# GATEWY_PCB.net
KiCad netlist of a schematic drawn in EAGLE
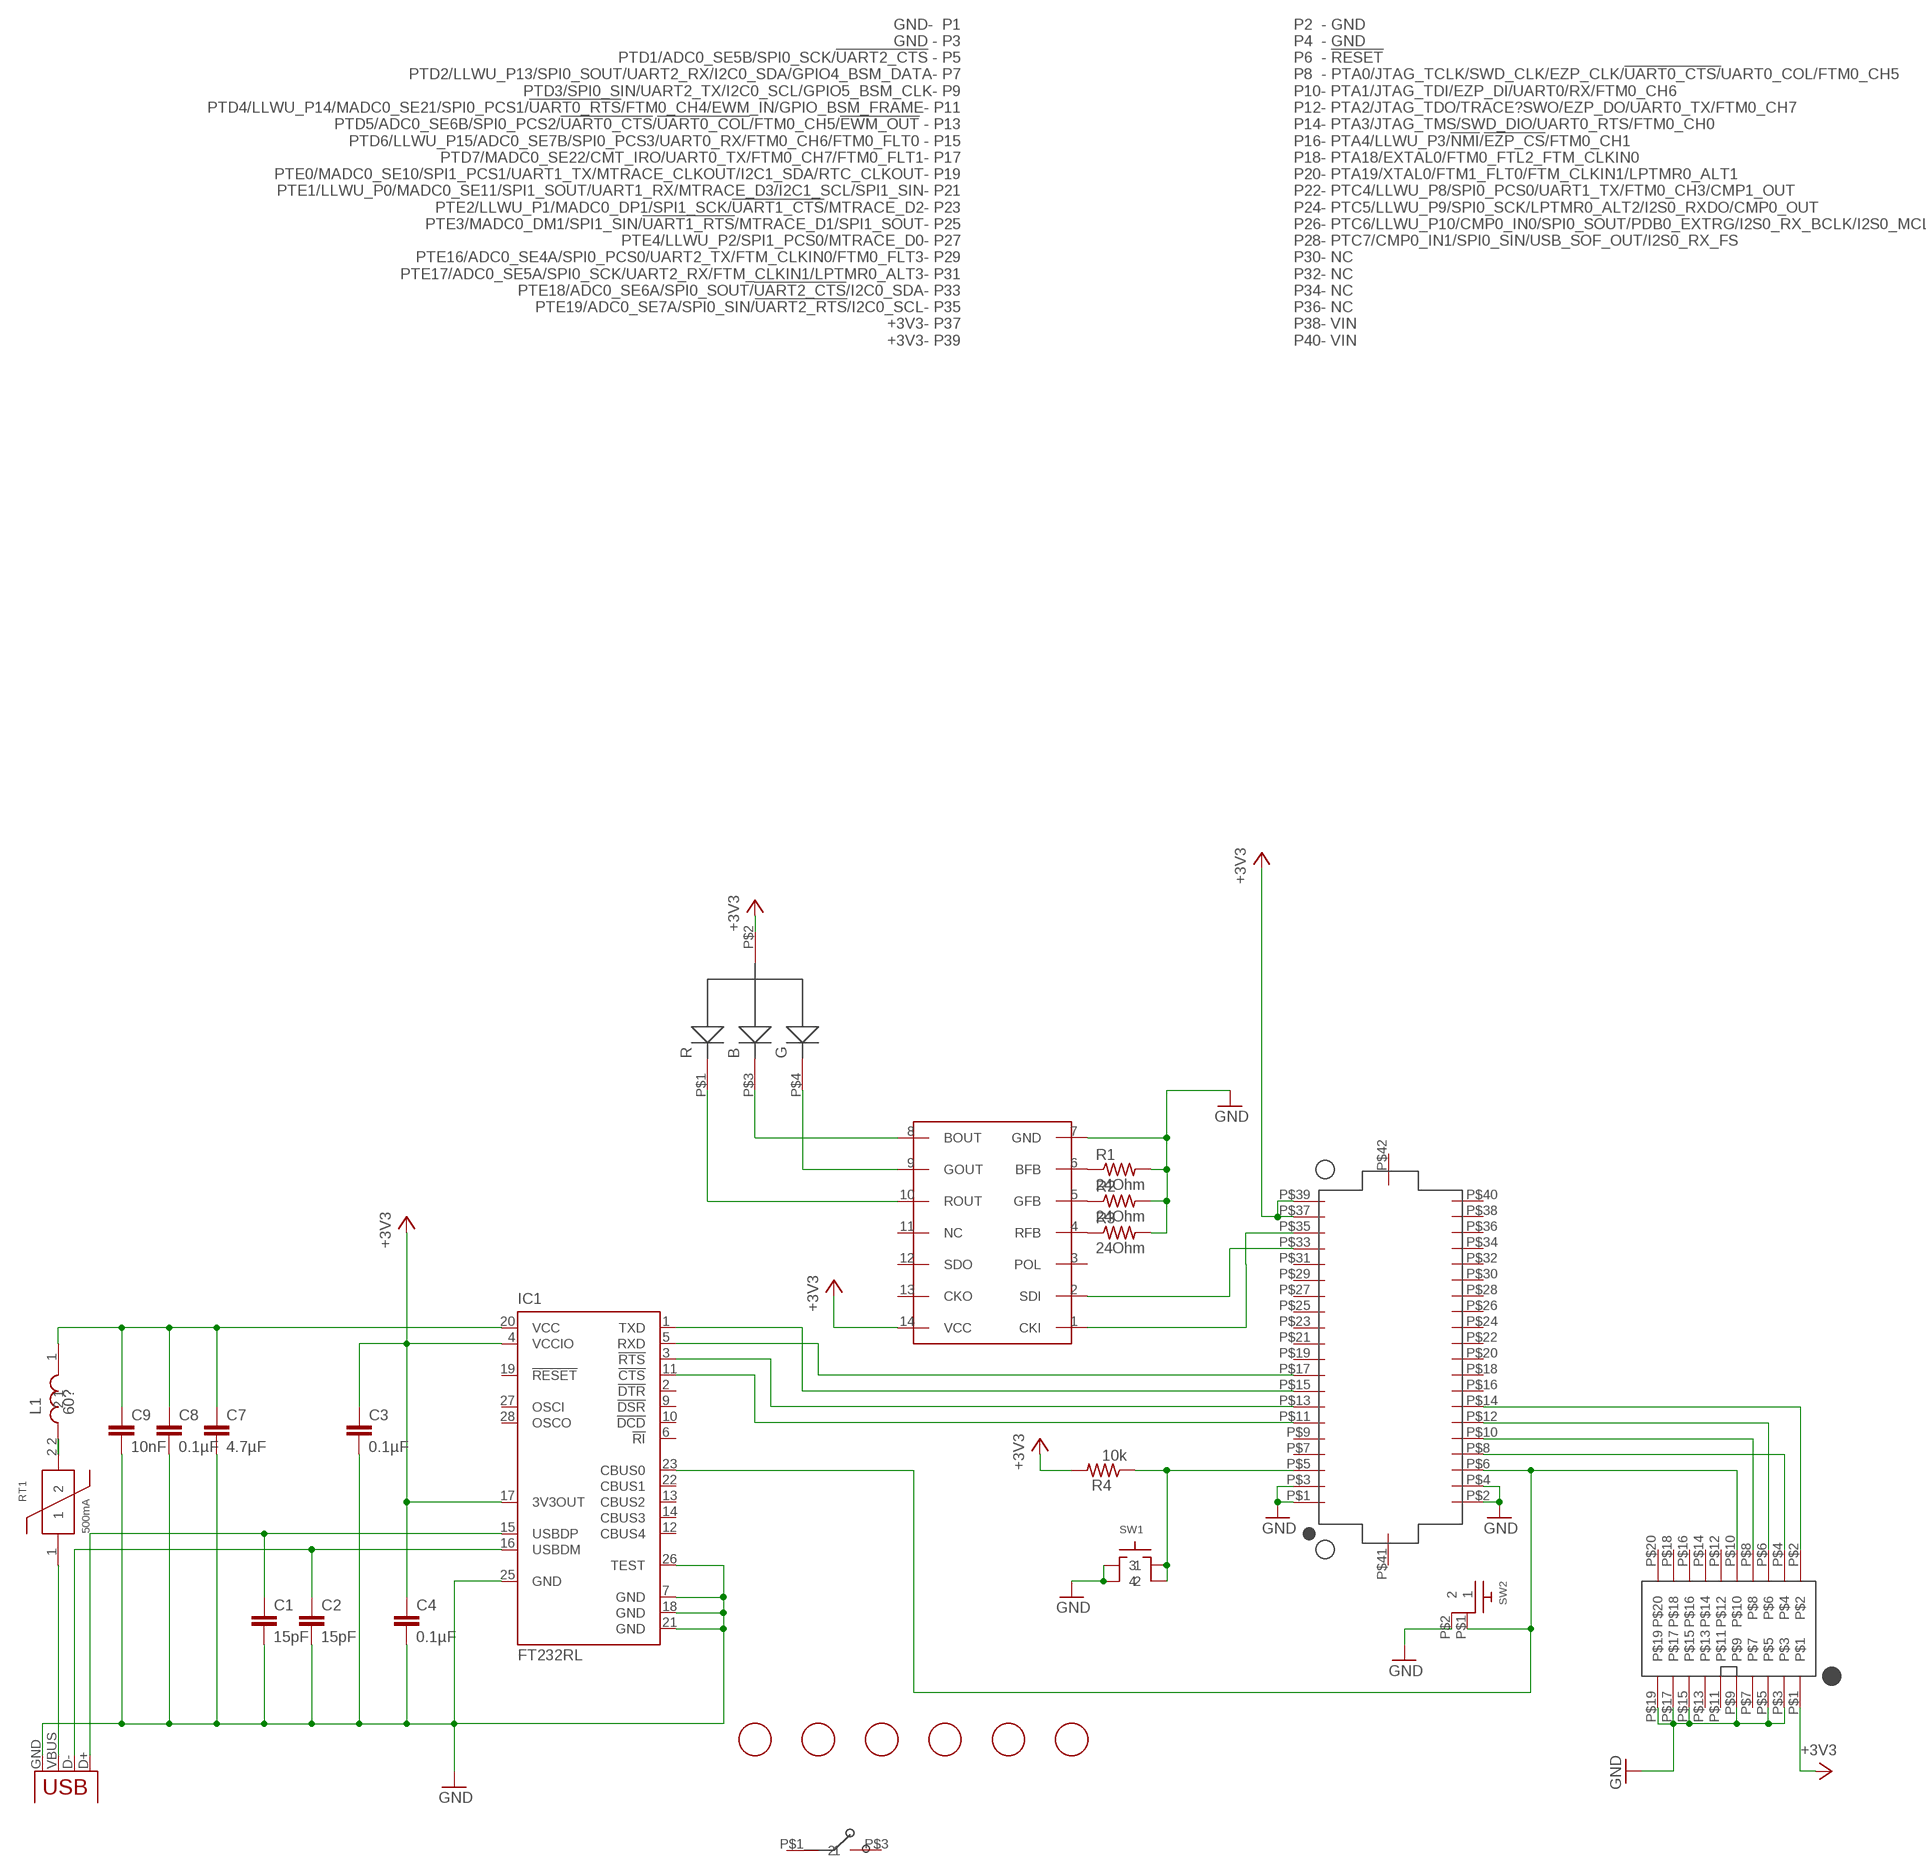
[diagram p0: schematic, sheet 1]

(export (version "E")
  (design (tool "Eeschema 10.0.6"))
  (components
    (comp (ref "AWESOME")
      (value "CJS")
      (footprint "eagle-import:CJS")
      (libsource (lib "eagle-import") (part "CJS"))
    )
    (comp (ref "C1")
      (value "15pF")
      (footprint "eagle-import:RF-C0402")
      (libsource (lib "eagle-import") (part "RF-C0402"))
    )
    (comp (ref "C2")
      (value "15pF")
      (footprint "eagle-import:RF-C0402")
      (libsource (lib "eagle-import") (part "RF-C0402"))
    )
    (comp (ref "C3")
      (value "0.1µF")
      (footprint "eagle-import:RF-C0402")
      (libsource (lib "eagle-import") (part "RF-C0402"))
    )
    (comp (ref "C4")
      (value "0.1µF")
      (footprint "eagle-import:RF-C0402")
      (libsource (lib "eagle-import") (part "RF-C0402"))
    )
    (comp (ref "C7")
      (value "4.7µF")
      (footprint "eagle-import:RF-C0805")
      (libsource (lib "eagle-import") (part "RF-C0805"))
    )
    (comp (ref "C8")
      (value "0.1µF")
      (footprint "eagle-import:RF-C0402")
      (libsource (lib "eagle-import") (part "RF-C0402"))
    )
    (comp (ref "C9")
      (value "10nF")
      (footprint "eagle-import:RF-C0402")
      (libsource (lib "eagle-import") (part "RF-C0402"))
    )
    (comp (ref "IC1")
      (value "FT232RL")
      (footprint "eagle-import:SSOP28")
      (libsource (lib "eagle-import") (part "FT232RL"))
    )
    (comp (ref "JTAG")
      (value "2X10JTAGSMD")
      (footprint "eagle-import:2X10JTAG-SMD")
      (libsource (lib "eagle-import") (part "2X10JTAGSMD"))
    )
    (comp (ref "KW2")
      (value "DF12_F")
      (footprint "eagle-import:DF12_F")
      (fields (field (name "MFGN") "Hirose") (field (name "MFGP") "DF12(3.0)-40DP-0.5V(86)"))
      (libsource (lib "eagle-import") (part "DF12_F"))
    )
    (comp (ref "L1")
      (value "60?")
      (footprint "eagle-import:RF-L0603")
      (libsource (lib "eagle-import") (part "RF-L0603"))
    )
    (comp (ref "LED1")
      (value "RGLBED")
      (footprint "eagle-import:RGBLED")
      (libsource (lib "eagle-import") (part "RGLBED"))
    )
    (comp (ref "R1")
      (value "24Ohm")
      (footprint "eagle-import:RF-C0805")
      (libsource (lib "eagle-import") (part "RF-R0805"))
    )
    (comp (ref "R2")
      (value "24Ohm")
      (footprint "eagle-import:RF-C0805")
      (libsource (lib "eagle-import") (part "RF-R0805"))
    )
    (comp (ref "R3")
      (value "24Ohm")
      (footprint "eagle-import:RF-C0805")
      (libsource (lib "eagle-import") (part "RF-R0805"))
    )
    (comp (ref "R4")
      (value "10k")
      (footprint "eagle-import:RF-C0805")
      (libsource (lib "eagle-import") (part "RF-R0805"))
    )
    (comp (ref "RT1")
      (value "500mA")
      (footprint "eagle-import:C1210")
      (libsource (lib "eagle-import") (part "SMD050F"))
    )
    (comp (ref "SW1")
      (value "SWITCH-TACTILE")
      (footprint "eagle-import:ESWITCH-TL3301PF")
      (libsource (lib "eagle-import") (part "SWITCH-TACTILE"))
    )
    (comp (ref "SW2")
      (value "RA_BUTTON")
      (footprint "eagle-import:RA_BUTTON")
      (libsource (lib "eagle-import") (part "RA_BUTTON"))
    )
    (comp (ref "U$14")
      (value "FIDUCIAL")
      (footprint "eagle-import:FIDUCIAL_1MM")
      (libsource (lib "eagle-import") (part "FIDUCIAL"))
    )
    (comp (ref "U$18")
      (value "FIDUCIAL")
      (footprint "eagle-import:FIDUCIAL_1MM")
      (libsource (lib "eagle-import") (part "FIDUCIAL"))
    )
    (comp (ref "U$25")
      (value "FIDUCIAL")
      (footprint "eagle-import:FIDUCIAL_1MM")
      (libsource (lib "eagle-import") (part "FIDUCIAL"))
    )
    (comp (ref "U$26")
      (value "FIDUCIAL")
      (footprint "eagle-import:FIDUCIAL_1MM")
      (libsource (lib "eagle-import") (part "FIDUCIAL"))
    )
    (comp (ref "U$27")
      (value "FIDUCIAL")
      (footprint "eagle-import:FIDUCIAL_1MM")
      (libsource (lib "eagle-import") (part "FIDUCIAL"))
    )
    (comp (ref "U$28")
      (value "FIDUCIAL")
      (footprint "eagle-import:FIDUCIAL_1MM")
      (libsource (lib "eagle-import") (part "FIDUCIAL"))
    )
    (comp (ref "U1")
      (value "WS2801")
      (footprint "eagle-import:SO14")
      (libsource (lib "eagle-import") (part "WS2801"))
    )
    (comp (ref "X1")
      (value "USBPTH")
      (footprint "eagle-import:USB-B-PTH")
      (libsource (lib "eagle-import") (part "USBPTH"))
    )
  )
  (nets
    (net (code "1") (name "+3V3") (class "Default")
      (node (ref "C3") (pin "1") (pinfunction "1_1") (pintype "passive"))
      (node (ref "C4") (pin "1") (pinfunction "1_1") (pintype "passive"))
      (node (ref "IC1") (pin "17") (pinfunction "3V3OUT_17") (pintype "output"))
      (node (ref "IC1") (pin "4") (pinfunction "VCCIO_4") (pintype "power_in"))
      (node (ref "JTAG") (pin "P$1") (pinfunction "P$1_P$1") (pintype "bidirectional"))
      (node (ref "KW2") (pin "P$37") (pinfunction "+3V3_P$37") (pintype "bidirectional"))
      (node (ref "KW2") (pin "P$39") (pinfunction "+3V3_P$39") (pintype "bidirectional"))
      (node (ref "LED1") (pin "P$2") (pinfunction "ANODE_P$2") (pintype "bidirectional"))
      (node (ref "R4") (pin "2") (pinfunction "2_2") (pintype "passive"))
      (node (ref "U1") (pin "14") (pinfunction "VCC_14") (pintype "bidirectional"))
    )
    (net (code "2") (name "GND") (class "Default")
      (node (ref "C1") (pin "2") (pinfunction "2_2") (pintype "passive"))
      (node (ref "C2") (pin "2") (pinfunction "2_2") (pintype "passive"))
      (node (ref "C3") (pin "2") (pinfunction "2_2") (pintype "passive"))
      (node (ref "C4") (pin "2") (pinfunction "2_2") (pintype "passive"))
      (node (ref "C7") (pin "2") (pinfunction "2_2") (pintype "passive"))
      (node (ref "C8") (pin "2") (pinfunction "2_2") (pintype "passive"))
      (node (ref "C9") (pin "2") (pinfunction "2_2") (pintype "passive"))
      (node (ref "IC1") (pin "18") (pinfunction "GND_18") (pintype "power_in"))
      (node (ref "IC1") (pin "21") (pinfunction "GND_21") (pintype "power_in"))
      (node (ref "IC1") (pin "25") (pinfunction "GND_25") (pintype "power_in"))
      (node (ref "IC1") (pin "26") (pinfunction "TEST_26") (pintype "input"))
      (node (ref "IC1") (pin "7") (pinfunction "GND_7") (pintype "power_in"))
      (node (ref "JTAG") (pin "P$15") (pinfunction "P$15_P$15") (pintype "bidirectional"))
      (node (ref "JTAG") (pin "P$17") (pinfunction "P$17_P$17") (pintype "bidirectional"))
      (node (ref "JTAG") (pin "P$19") (pinfunction "P$19_P$19") (pintype "bidirectional"))
      (node (ref "JTAG") (pin "P$3") (pinfunction "P$3_P$3") (pintype "bidirectional"))
      (node (ref "JTAG") (pin "P$5") (pinfunction "P$5_P$5") (pintype "bidirectional"))
      (node (ref "JTAG") (pin "P$9") (pinfunction "P$9_P$9") (pintype "bidirectional"))
      (node (ref "KW2") (pin "P$1") (pinfunction "GND_P$1") (pintype "bidirectional"))
      (node (ref "KW2") (pin "P$2") (pinfunction "GND_P$2") (pintype "bidirectional"))
      (node (ref "KW2") (pin "P$3") (pinfunction "GND_P$3") (pintype "bidirectional"))
      (node (ref "KW2") (pin "P$4") (pinfunction "GND_P$4") (pintype "bidirectional"))
      (node (ref "R1") (pin "2") (pinfunction "2_2") (pintype "passive"))
      (node (ref "R2") (pin "2") (pinfunction "2_2") (pintype "passive"))
      (node (ref "R3") (pin "2") (pinfunction "2_2") (pintype "passive"))
      (node (ref "SW1") (pin "1") (pinfunction "1_1") (pintype "input"))
      (node (ref "SW1") (pin "2") (pinfunction "2_2") (pintype "input"))
      (node (ref "SW2") (pin "P$2") (pinfunction "2_P$2") (pintype "input"))
      (node (ref "U1") (pin "7") (pinfunction "GND_7") (pintype "bidirectional"))
      (node (ref "X1") (pin "GND") (pinfunction "GND_GND") (pintype "bidirectional"))
    )
    (net (code "3") (name "Net-(IC1-CBUS0)") (class "Default")
      (node (ref "IC1") (pin "23") (pinfunction "CBUS0_23") (pintype "bidirectional"))
      (node (ref "JTAG") (pin "P$10") (pinfunction "P$10_P$10") (pintype "bidirectional"))
      (node (ref "KW2") (pin "P$6") (pinfunction "~{RESET}_P$6") (pintype "bidirectional"))
      (node (ref "SW2") (pin "P$1") (pinfunction "1_P$1") (pintype "input"))
    )
    (net (code "4") (name "Net-(IC1-RXD)") (class "Default")
      (node (ref "IC1") (pin "5") (pinfunction "RXD_5") (pintype "input"))
      (node (ref "KW2") (pin "P$17") (pinfunction "PTD7/MADC0_SE22/CMT_IRO/UART0_TX/FTM0_CH7/FTM0_FLT1_P$17") (pintype "bidirectional"))
    )
    (net (code "5") (name "Net-(IC1-TXD)") (class "Default")
      (node (ref "IC1") (pin "1") (pinfunction "TXD_1") (pintype "output"))
      (node (ref "KW2") (pin "P$15") (pinfunction "PTD6/LLWU_P15/ADC0_SE7B/SPI0_PCS3/UART0_RX/FTM0_CH6/FTM0_FLT0_P$15") (pintype "bidirectional"))
    )
    (net (code "6") (name "Net-(IC1-USBDM)") (class "Default")
      (node (ref "C2") (pin "1") (pinfunction "1_1") (pintype "passive"))
      (node (ref "IC1") (pin "16") (pinfunction "USBDM_16") (pintype "bidirectional"))
      (node (ref "X1") (pin "D-") (pinfunction "D-_D-") (pintype "bidirectional"))
    )
    (net (code "7") (name "Net-(IC1-USBDP)") (class "Default")
      (node (ref "C1") (pin "1") (pinfunction "1_1") (pintype "passive"))
      (node (ref "IC1") (pin "15") (pinfunction "USBDP_15") (pintype "bidirectional"))
      (node (ref "X1") (pin "D+") (pinfunction "D+_D+") (pintype "bidirectional"))
    )
    (net (code "8") (name "Net-(IC1-VCC)") (class "Default")
      (node (ref "C7") (pin "1") (pinfunction "1_1") (pintype "passive"))
      (node (ref "C8") (pin "1") (pinfunction "1_1") (pintype "passive"))
      (node (ref "C9") (pin "1") (pinfunction "1_1") (pintype "passive"))
      (node (ref "IC1") (pin "20") (pinfunction "VCC_20") (pintype "power_in"))
      (node (ref "L1") (pin "1") (pinfunction "1_1") (pintype "bidirectional"))
    )
    (net (code "9") (name "Net-(IC1-~{CTS})") (class "Default")
      (node (ref "IC1") (pin "11") (pinfunction "~{CTS}_11") (pintype "input"))
      (node (ref "KW2") (pin "P$11") (pinfunction "PTD4/LLWU_P14/MADC0_SE21/SPI0_PCS1/~{UART0_RTS}/FTM0_CH4/EWM_IN/GPIO_BSM_FRAME_P$11") (pintype "bidirectional"))
    )
    (net (code "10") (name "Net-(IC1-~{RTS})") (class "Default")
      (node (ref "IC1") (pin "3") (pinfunction "~{RTS}_3") (pintype "output"))
      (node (ref "KW2") (pin "P$13") (pinfunction "PTD5/ADC0_SE6B/SPI0_PCS2/~{UART0_CTS}/~{UART0_COL}/FTM0_CH5/~{EWM_OUT}_P$13") (pintype "bidirectional"))
    )
    (net (code "11") (name "Net-(KW2-PTA0{slash}JTAG_TCLK{slash}SWD_CLK{slash}EZP_CLK{slash}~{UART0_CTS{slash}}UART0_COL{slash}FTM0_CH5)") (class "Default")
      (node (ref "JTAG") (pin "P$4") (pinfunction "P$4_P$4") (pintype "bidirectional"))
      (node (ref "KW2") (pin "P$8") (pinfunction "PTA0/JTAG_TCLK/SWD_CLK/EZP_CLK/~{UART0_CTS/}UART0_COL/FTM0_CH5_P$8") (pintype "bidirectional"))
    )
    (net (code "12") (name "Net-(KW2-PTA1{slash}JTAG_TDI{slash}EZP_DI{slash}UART0{slash}RX{slash}FTM0_CH6)") (class "Default")
      (node (ref "JTAG") (pin "P$8") (pinfunction "P$8_P$8") (pintype "bidirectional"))
      (node (ref "KW2") (pin "P$10") (pinfunction "PTA1/JTAG_TDI/EZP_DI/UART0/RX/FTM0_CH6_P$10") (pintype "bidirectional"))
    )
    (net (code "13") (name "Net-(KW2-PTA2{slash}JTAG_TDO{slash}TRACE?SWO{slash}EZP_DO{slash}UART0_TX{slash}FTM0_CH7)") (class "Default")
      (node (ref "JTAG") (pin "P$6") (pinfunction "P$6_P$6") (pintype "bidirectional"))
      (node (ref "KW2") (pin "P$12") (pinfunction "PTA2/JTAG_TDO/TRACE?SWO/EZP_DO/UART0_TX/FTM0_CH7_P$12") (pintype "bidirectional"))
    )
    (net (code "14") (name "Net-(KW2-PTA3{slash}JTAG_TMS{slash}SWD_DIO{slash}UART0_RTS{slash}FTM0_CH0)") (class "Default")
      (node (ref "JTAG") (pin "P$2") (pinfunction "P$2_P$2") (pintype "bidirectional"))
      (node (ref "KW2") (pin "P$14") (pinfunction "PTA3/JTAG_TMS/SWD_DIO/UART0_RTS/FTM0_CH0_P$14") (pintype "bidirectional"))
    )
    (net (code "15") (name "Net-(KW2-PTD1{slash}ADC0_SE5B{slash}SPI0_SCK{slash}~{UART2_CTS})") (class "Default")
      (node (ref "KW2") (pin "P$5") (pinfunction "PTD1/ADC0_SE5B/SPI0_SCK/~{UART2_CTS}_P$5") (pintype "bidirectional"))
      (node (ref "R4") (pin "1") (pinfunction "1_1") (pintype "passive"))
      (node (ref "SW1") (pin "3") (pinfunction "3_3") (pintype "input"))
      (node (ref "SW1") (pin "4") (pinfunction "4_4") (pintype "input"))
    )
    (net (code "16") (name "Net-(KW2-PTE18{slash}ADC0_SE6A{slash}SPI0_SOUT{slash}~{UART2_CTS}{slash}I2C0_SDA)") (class "Default")
      (node (ref "KW2") (pin "P$33") (pinfunction "PTE18/ADC0_SE6A/SPI0_SOUT/~{UART2_CTS}/I2C0_SDA_P$33") (pintype "bidirectional"))
      (node (ref "U1") (pin "2") (pinfunction "SDI_2") (pintype "bidirectional"))
    )
    (net (code "17") (name "Net-(KW2-PTE19{slash}ADC0_SE7A{slash}SPI0_SIN{slash}~{UART2_RTS}{slash}I2C0_SCL)") (class "Default")
      (node (ref "KW2") (pin "P$35") (pinfunction "PTE19/ADC0_SE7A/SPI0_SIN/~{UART2_RTS}/I2C0_SCL_P$35") (pintype "bidirectional"))
      (node (ref "U1") (pin "1") (pinfunction "CKI_1") (pintype "bidirectional"))
    )
    (net (code "18") (name "Net-(L1-Pad2)") (class "Default")
      (node (ref "L1") (pin "2") (pinfunction "2_2") (pintype "bidirectional"))
      (node (ref "RT1") (pin "2") (pinfunction "2_2") (pintype "bidirectional"))
    )
    (net (code "19") (name "Net-(LED1-BLUE)") (class "Default")
      (node (ref "LED1") (pin "P$3") (pinfunction "BLUE_P$3") (pintype "bidirectional"))
      (node (ref "U1") (pin "8") (pinfunction "BOUT_8") (pintype "bidirectional"))
    )
    (net (code "20") (name "Net-(LED1-GREEN)") (class "Default")
      (node (ref "LED1") (pin "P$4") (pinfunction "GREEN_P$4") (pintype "bidirectional"))
      (node (ref "U1") (pin "9") (pinfunction "GOUT_9") (pintype "bidirectional"))
    )
    (net (code "21") (name "Net-(LED1-RED)") (class "Default")
      (node (ref "LED1") (pin "P$1") (pinfunction "RED_P$1") (pintype "bidirectional"))
      (node (ref "U1") (pin "10") (pinfunction "ROUT_10") (pintype "bidirectional"))
    )
    (net (code "22") (name "Net-(RT1-Pad1)") (class "Default")
      (node (ref "RT1") (pin "1") (pinfunction "1_1") (pintype "bidirectional"))
      (node (ref "X1") (pin "VBUS") (pinfunction "VBUS_VBUS") (pintype "bidirectional"))
    )
    (net (code "23") (name "Net-(U1-BFB)") (class "Default")
      (node (ref "R1") (pin "1") (pinfunction "1_1") (pintype "passive"))
      (node (ref "U1") (pin "6") (pinfunction "BFB_6") (pintype "bidirectional"))
    )
    (net (code "24") (name "Net-(U1-GFB)") (class "Default")
      (node (ref "R2") (pin "1") (pinfunction "1_1") (pintype "passive"))
      (node (ref "U1") (pin "5") (pinfunction "GFB_5") (pintype "bidirectional"))
    )
    (net (code "25") (name "Net-(U1-RFB)") (class "Default")
      (node (ref "R3") (pin "1") (pinfunction "1_1") (pintype "passive"))
      (node (ref "U1") (pin "4") (pinfunction "RFB_4") (pintype "bidirectional"))
    )
    (net (code "26") (name "unconnected-(AWESOME-1-PadP$1)") (class "Default")
      (node (ref "AWESOME") (pin "P$1") (pinfunction "1_P$1") (pintype "bidirectional"))
    )
    (net (code "27") (name "unconnected-(AWESOME-2-PadP$3)") (class "Default")
      (node (ref "AWESOME") (pin "P$3") (pinfunction "2_P$3") (pintype "bidirectional"))
    )
    (net (code "28") (name "unconnected-(IC1-CBUS1-Pad22)") (class "Default")
      (node (ref "IC1") (pin "22") (pinfunction "CBUS1_22") (pintype "bidirectional"))
    )
    (net (code "29") (name "unconnected-(IC1-CBUS2-Pad13)") (class "Default")
      (node (ref "IC1") (pin "13") (pinfunction "CBUS2_13") (pintype "bidirectional"))
    )
    (net (code "30") (name "unconnected-(IC1-CBUS3-Pad14)") (class "Default")
      (node (ref "IC1") (pin "14") (pinfunction "CBUS3_14") (pintype "bidirectional"))
    )
    (net (code "31") (name "unconnected-(IC1-CBUS4-Pad12)") (class "Default")
      (node (ref "IC1") (pin "12") (pinfunction "CBUS4_12") (pintype "bidirectional"))
    )
    (net (code "32") (name "unconnected-(IC1-OSCI-Pad27)") (class "Default")
      (node (ref "IC1") (pin "27") (pinfunction "OSCI_27") (pintype "input"))
    )
    (net (code "33") (name "unconnected-(IC1-OSCO-Pad28)") (class "Default")
      (node (ref "IC1") (pin "28") (pinfunction "OSCO_28") (pintype "output"))
    )
    (net (code "34") (name "unconnected-(IC1-~{DCD}-Pad10)") (class "Default")
      (node (ref "IC1") (pin "10") (pinfunction "~{DCD}_10") (pintype "input"))
    )
    (net (code "35") (name "unconnected-(IC1-~{DSR}-Pad9)") (class "Default")
      (node (ref "IC1") (pin "9") (pinfunction "~{DSR}_9") (pintype "input"))
    )
    (net (code "36") (name "unconnected-(IC1-~{DTR}-Pad2)") (class "Default")
      (node (ref "IC1") (pin "2") (pinfunction "~{DTR}_2") (pintype "output"))
    )
    (net (code "37") (name "unconnected-(IC1-~{RESET}-Pad19)") (class "Default")
      (node (ref "IC1") (pin "19") (pinfunction "~{RESET}_19") (pintype "input"))
    )
    (net (code "38") (name "unconnected-(IC1-~{RI}-Pad6)") (class "Default")
      (node (ref "IC1") (pin "6") (pinfunction "~{RI}_6") (pintype "input"))
    )
    (net (code "39") (name "unconnected-(JTAG-PadP$7)") (class "Default")
      (node (ref "JTAG") (pin "P$7") (pinfunction "P$7_P$7") (pintype "bidirectional"))
    )
    (net (code "40") (name "unconnected-(JTAG-PadP$11)") (class "Default")
      (node (ref "JTAG") (pin "P$11") (pinfunction "P$11_P$11") (pintype "bidirectional"))
    )
    (net (code "41") (name "unconnected-(JTAG-PadP$12)") (class "Default")
      (node (ref "JTAG") (pin "P$12") (pinfunction "P$12_P$12") (pintype "bidirectional"))
    )
    (net (code "42") (name "unconnected-(JTAG-PadP$13)") (class "Default")
      (node (ref "JTAG") (pin "P$13") (pinfunction "P$13_P$13") (pintype "bidirectional"))
    )
    (net (code "43") (name "unconnected-(JTAG-PadP$14)") (class "Default")
      (node (ref "JTAG") (pin "P$14") (pinfunction "P$14_P$14") (pintype "bidirectional"))
    )
    (net (code "44") (name "unconnected-(JTAG-PadP$16)") (class "Default")
      (node (ref "JTAG") (pin "P$16") (pinfunction "P$16_P$16") (pintype "bidirectional"))
    )
    (net (code "45") (name "unconnected-(JTAG-PadP$18)") (class "Default")
      (node (ref "JTAG") (pin "P$18") (pinfunction "P$18_P$18") (pintype "bidirectional"))
    )
    (net (code "46") (name "unconnected-(JTAG-PadP$20)") (class "Default")
      (node (ref "JTAG") (pin "P$20") (pinfunction "P$20_P$20") (pintype "bidirectional"))
    )
    (net (code "47") (name "unconnected-(KW2-NC-PadP$30)") (class "Default")
      (node (ref "KW2") (pin "P$30") (pinfunction "NC_P$30") (pintype "bidirectional"))
    )
    (net (code "48") (name "unconnected-(KW2-NC-PadP$32)") (class "Default")
      (node (ref "KW2") (pin "P$32") (pinfunction "NC_P$32") (pintype "bidirectional"))
    )
    (net (code "49") (name "unconnected-(KW2-NC-PadP$34)") (class "Default")
      (node (ref "KW2") (pin "P$34") (pinfunction "NC_P$34") (pintype "bidirectional"))
    )
    (net (code "50") (name "unconnected-(KW2-NC-PadP$36)") (class "Default")
      (node (ref "KW2") (pin "P$36") (pinfunction "NC_P$36") (pintype "bidirectional"))
    )
    (net (code "51") (name "unconnected-(KW2-PTA4{slash}LLWU_P3{slash}~{NMI}{slash}~{EZP_CS}{slash}FTM0_CH1-PadP$16)") (class "Default")
      (node (ref "KW2") (pin "P$16") (pinfunction "PTA4/LLWU_P3/~{NMI}/~{EZP_CS}/FTM0_CH1_P$16") (pintype "bidirectional"))
    )
    (net (code "52") (name "unconnected-(KW2-PTA18{slash}EXTAL0{slash}FTM0_FTL2_FTM_CLKIN0-PadP$18)") (class "Default")
      (node (ref "KW2") (pin "P$18") (pinfunction "PTA18/EXTAL0/FTM0_FTL2_FTM_CLKIN0_P$18") (pintype "bidirectional"))
    )
    (net (code "53") (name "unconnected-(KW2-PTA19{slash}XTAL0{slash}FTM1_FLT0{slash}FTM_CLKIN1{slash}LPTMR0_ALT1-PadP$20)") (class "Default")
      (node (ref "KW2") (pin "P$20") (pinfunction "PTA19/XTAL0/FTM1_FLT0/FTM_CLKIN1/LPTMR0_ALT1_P$20") (pintype "bidirectional"))
    )
    (net (code "54") (name "unconnected-(KW2-PTC4{slash}LLWU_P8{slash}SPI0_PCS0{slash}UART1_TX{slash}FTM0_CH3{slash}CMP1_OUT-PadP$22)") (class "Default")
      (node (ref "KW2") (pin "P$22") (pinfunction "PTC4/LLWU_P8/SPI0_PCS0/UART1_TX/FTM0_CH3/CMP1_OUT_P$22") (pintype "bidirectional"))
    )
    (net (code "55") (name "unconnected-(KW2-PTC5{slash}LLWU_P8{slash}SPI0_PCS0{slash}UART1_TX{slash}FTM0_CH3{slash}CMP1_OUT-PadP$24)") (class "Default")
      (node (ref "KW2") (pin "P$24") (pinfunction "PTC5/LLWU_P8/SPI0_PCS0/UART1_TX/FTM0_CH3/CMP1_OUT_P$24") (pintype "bidirectional"))
    )
    (net (code "56") (name "unconnected-(KW2-PTC6{slash}LLWU_P10{slash}CMP0_IN0{slash}SPI0_SOUT{slash}PDB0_EXTRG{slash}I2S0_RX_BCLK{slash}I2S0_MCLK-PadP$26)") (class "Default")
      (node (ref "KW2") (pin "P$26") (pinfunction "PTC6/LLWU_P10/CMP0_IN0/SPI0_SOUT/PDB0_EXTRG/I2S0_RX_BCLK/I2S0_MCLK_P$26") (pintype "bidirectional"))
    )
    (net (code "57") (name "unconnected-(KW2-PTC7{slash}CMP0_IN1{slash}SPI0_SIN{slash}USB_SOF_OUT{slash}I2S0_RX_FS-PadP$28)") (class "Default")
      (node (ref "KW2") (pin "P$28") (pinfunction "PTC7/CMP0_IN1/SPI0_SIN/USB_SOF_OUT/I2S0_RX_FS_P$28") (pintype "bidirectional"))
    )
    (net (code "58") (name "unconnected-(KW2-PTD2{slash}LLWU_P13{slash}SPI0_SOUT{slash}UART2_RX{slash}I2C0_SDA{slash}GPIO4_BSM_DATA-PadP$7)") (class "Default")
      (node (ref "KW2") (pin "P$7") (pinfunction "PTD2/LLWU_P13/SPI0_SOUT/UART2_RX/I2C0_SDA/GPIO4_BSM_DATA_P$7") (pintype "bidirectional"))
    )
    (net (code "59") (name "unconnected-(KW2-PTD3{slash}SPI0_SIN{slash}UART2_TX{slash}I2C0_SCL{slash}GPIO5_BSM_CLK-PadP$9)") (class "Default")
      (node (ref "KW2") (pin "P$9") (pinfunction "PTD3/SPI0_SIN/UART2_TX/I2C0_SCL/GPIO5_BSM_CLK_P$9") (pintype "bidirectional"))
    )
    (net (code "60") (name "unconnected-(KW2-PTE0{slash}MADC0_SE10{slash}SPI1_PCS1{slash}UART1_TX{slash}MTRACE_CLKOUT{slash}I2C1_SDA{slash}RTC_CLKOUT-PadP$19)") (class "Default")
      (node (ref "KW2") (pin "P$19") (pinfunction "PTE0/MADC0_SE10/SPI1_PCS1/UART1_TX/MTRACE_CLKOUT/I2C1_SDA/RTC_CLKOUT_P$19") (pintype "bidirectional"))
    )
    (net (code "61") (name "unconnected-(KW2-PTE1{slash}LLWU_P0{slash}MADC0_SE11{slash}SPI1_SOUT{slash}UART1_RX{slash}MTRACE_D3{slash}I2C1_SCL{slash}SPI1_SIN-PadP$21)") (class "Default")
      (node (ref "KW2") (pin "P$21") (pinfunction "PTE1/LLWU_P0/MADC0_SE11/SPI1_SOUT/UART1_RX/MTRACE_D3/I2C1_SCL/SPI1_SIN_P$21") (pintype "bidirectional"))
    )
    (net (code "62") (name "unconnected-(KW2-PTE2{slash}LLWU_P1{slash}MADC0_DP1{slash}SPI1_SCK{slash}~{UART1_CTS}{slash}MTRACE_D2-PadP$23)") (class "Default")
      (node (ref "KW2") (pin "P$23") (pinfunction "PTE2/LLWU_P1/MADC0_DP1/SPI1_SCK/~{UART1_CTS}/MTRACE_D2_P$23") (pintype "bidirectional"))
    )
    (net (code "63") (name "unconnected-(KW2-PTE3{slash}MADC0_DM1{slash}SPI1_SIN{slash}~{UART1_RTS}{slash}MTRACE_D1{slash}SPI1_SOUT-PadP$25)") (class "Default")
      (node (ref "KW2") (pin "P$25") (pinfunction "PTE3/MADC0_DM1/SPI1_SIN/~{UART1_RTS}/MTRACE_D1/SPI1_SOUT_P$25") (pintype "bidirectional"))
    )
    (net (code "64") (name "unconnected-(KW2-PTE4{slash}LLWU_P2{slash}SPI1_PCS0{slash}MTRACE_D0-PadP$27)") (class "Default")
      (node (ref "KW2") (pin "P$27") (pinfunction "PTE4/LLWU_P2/SPI1_PCS0/MTRACE_D0_P$27") (pintype "bidirectional"))
    )
    (net (code "65") (name "unconnected-(KW2-PTE16{slash}ADC0_SE4A{slash}SPI0_PCS0{slash}UART2_TX{slash}FTM_CLKIN0{slash}FTM0_FLT3-PadP$29)") (class "Default")
      (node (ref "KW2") (pin "P$29") (pinfunction "PTE16/ADC0_SE4A/SPI0_PCS0/UART2_TX/FTM_CLKIN0/FTM0_FLT3_P$29") (pintype "bidirectional"))
    )
    (net (code "66") (name "unconnected-(KW2-PTE17{slash}ADC0_SE5A{slash}SPI0_SCK{slash}UART2_RX{slash}FTM_CLKIN1{slash}LPTMR0_ALT3-PadP$31)") (class "Default")
      (node (ref "KW2") (pin "P$31") (pinfunction "PTE17/ADC0_SE5A/SPI0_SCK/UART2_RX/FTM_CLKIN1/LPTMR0_ALT3_P$31") (pintype "bidirectional"))
    )
    (net (code "67") (name "unconnected-(KW2-PadP$41)") (class "Default")
      (node (ref "KW2") (pin "P$41") (pinfunction "P$41_P$41") (pintype "bidirectional"))
    )
    (net (code "68") (name "unconnected-(KW2-PadP$42)") (class "Default")
      (node (ref "KW2") (pin "P$42") (pinfunction "P$42_P$42") (pintype "bidirectional"))
    )
    (net (code "69") (name "unconnected-(KW2-VIN-PadP$38)") (class "Default")
      (node (ref "KW2") (pin "P$38") (pinfunction "VIN_P$38") (pintype "bidirectional"))
    )
    (net (code "70") (name "unconnected-(KW2-VIN-PadP$40)") (class "Default")
      (node (ref "KW2") (pin "P$40") (pinfunction "VIN_P$40") (pintype "bidirectional"))
    )
    (net (code "71") (name "unconnected-(U1-CKO-Pad13)") (class "Default")
      (node (ref "U1") (pin "13") (pinfunction "CKO_13") (pintype "bidirectional"))
    )
    (net (code "72") (name "unconnected-(U1-NC-Pad11)") (class "Default")
      (node (ref "U1") (pin "11") (pinfunction "NC_11") (pintype "bidirectional"))
    )
    (net (code "73") (name "unconnected-(U1-POL-Pad3)") (class "Default")
      (node (ref "U1") (pin "3") (pinfunction "POL_3") (pintype "bidirectional"))
    )
    (net (code "74") (name "unconnected-(U1-SDO-Pad12)") (class "Default")
      (node (ref "U1") (pin "12") (pinfunction "SDO_12") (pintype "bidirectional"))
    )
  )
)
